# SAS_rev04.net
KiCad netlist of a schematic drawn in EAGLE
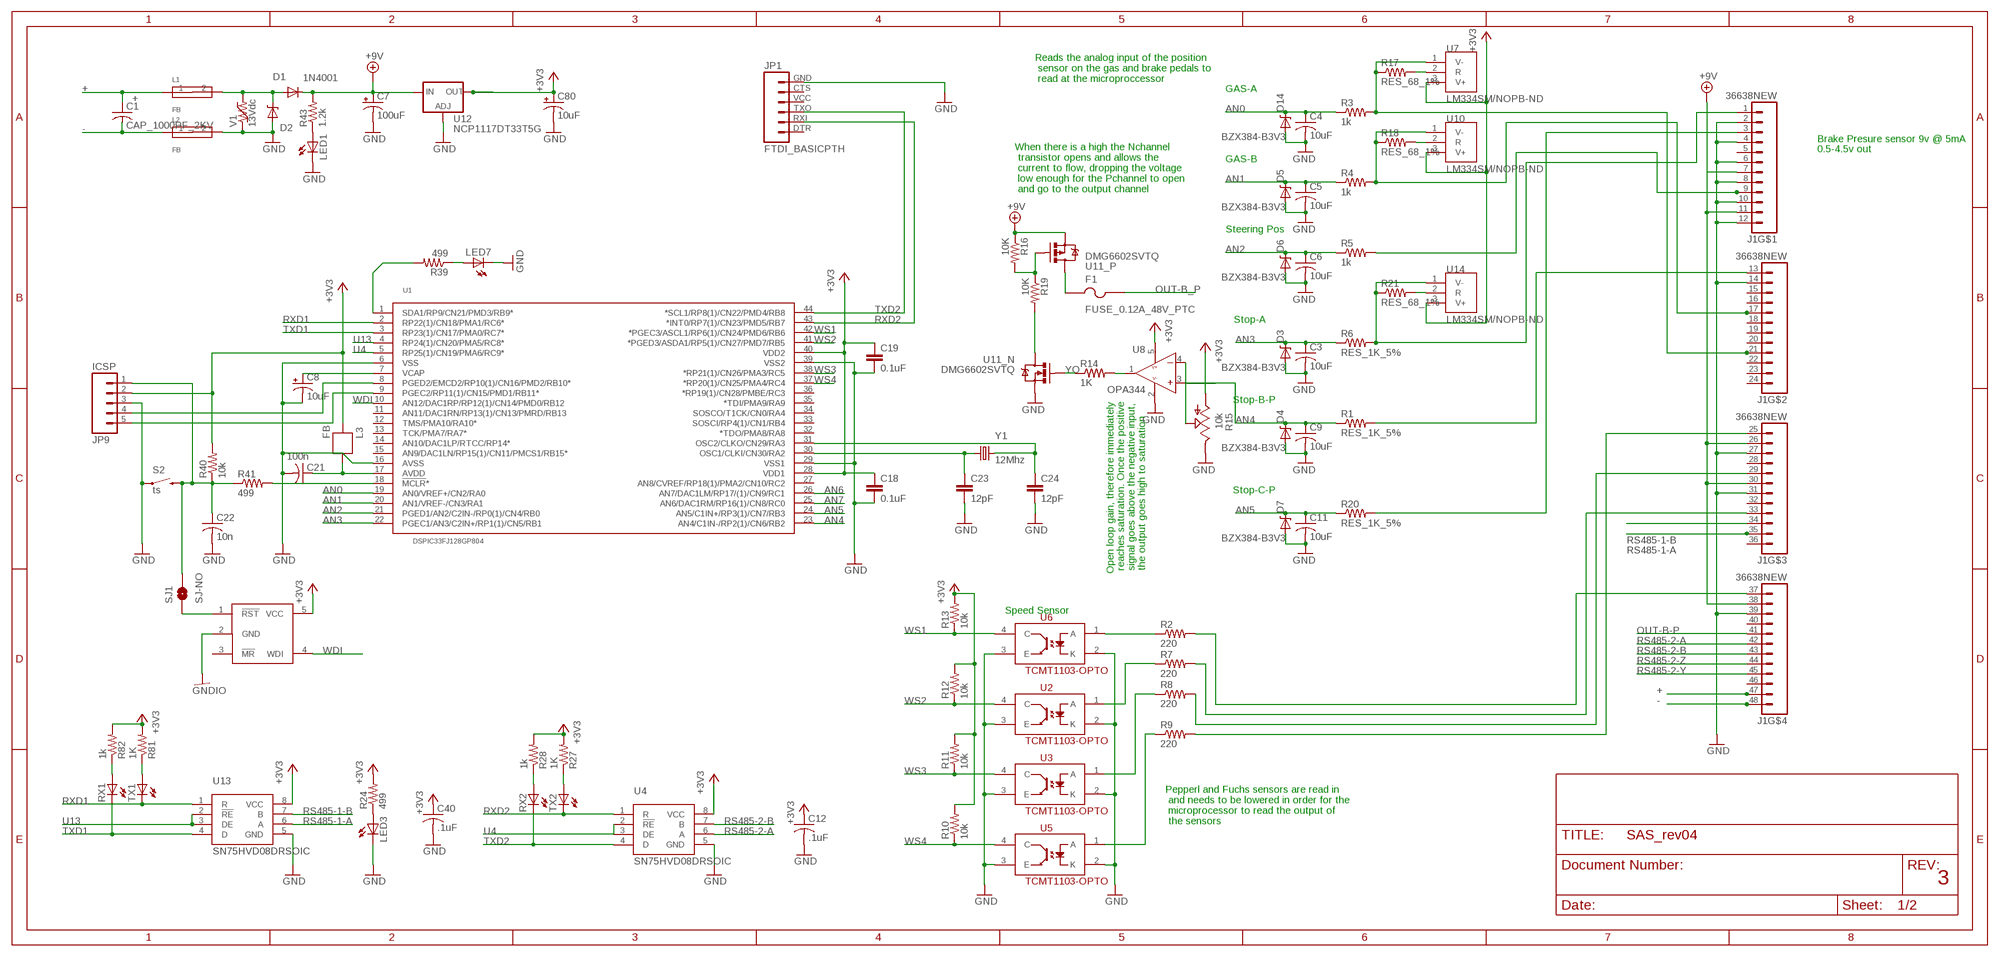
[diagram p0: schematic, sheet 1]

(export (version "E")
  (design (tool "Eeschema 10.0.6"))
  (components
    (comp (ref "C1")
      (value "CAP_1000PF_2KV")
      (footprint "eagle-import:C1825")
      (fields (field (name "PARTNO") "1825GC102KAT1A"))
      (libsource (lib "eagle-import") (part "CAP_1000PF_2KV"))
    )
    (comp (ref "C3")
      (value "10uF")
      (footprint "eagle-import:C0805")
      (libsource (lib "eagle-import") (part "C-USC0805"))
    )
    (comp (ref "C4")
      (value "10uF")
      (footprint "eagle-import:C0805")
      (libsource (lib "eagle-import") (part "C-USC0805"))
    )
    (comp (ref "C5")
      (value "10uF")
      (footprint "eagle-import:C0805")
      (libsource (lib "eagle-import") (part "C-USC0805"))
    )
    (comp (ref "C6")
      (value "10uF")
      (footprint "eagle-import:C0805")
      (libsource (lib "eagle-import") (part "C-USC0805"))
    )
    (comp (ref "C7")
      (value "100uF")
      (footprint "eagle-import:EIA7343")
      (libsource (lib "eagle-import") (part "CAP_POL7343"))
    )
    (comp (ref "C8")
      (value "10uF")
      (footprint "eagle-import:EIA3216-16V")
      (fields (field (name "PARTNO") "T491A106M016AT"))
      (libsource (lib "eagle-import") (part "CAP-POL_10UF_16V"))
    )
    (comp (ref "C9")
      (value "10uF")
      (footprint "eagle-import:C0805")
      (libsource (lib "eagle-import") (part "C-USC0805"))
    )
    (comp (ref "C11")
      (value "10uF")
      (footprint "eagle-import:C0805")
      (libsource (lib "eagle-import") (part "C-USC0805"))
    )
    (comp (ref "C12")
      (value ".1uF")
      (footprint "eagle-import:0603")
      (fields (field (name "PARTNO") "CC0603ZRY5V9BB104"))
      (libsource (lib "eagle-import") (part "CAP_0.1UF_50V"))
    )
    (comp (ref "C18")
      (value "0.1uF")
      (footprint "eagle-import:0805")
      (libsource (lib "eagle-import") (part "CAP0805"))
    )
    (comp (ref "C19")
      (value "0.1uF")
      (footprint "eagle-import:0805")
      (libsource (lib "eagle-import") (part "CAP0805"))
    )
    (comp (ref "C21")
      (value "100n")
      (footprint "eagle-import:C0805")
      (libsource (lib "eagle-import") (part "C-USC0805"))
    )
    (comp (ref "C22")
      (value "10n")
      (footprint "eagle-import:0603")
      (fields (field (name "PARTNO") "CL10F103ZB8NNNC"))
      (libsource (lib "eagle-import") (part "CAP_10NF_50V"))
    )
    (comp (ref "C23")
      (value "12pF")
      (footprint "eagle-import:0805")
      (libsource (lib "eagle-import") (part "CAP0805"))
    )
    (comp (ref "C24")
      (value "12pF")
      (footprint "eagle-import:0805")
      (libsource (lib "eagle-import") (part "CAP0805"))
    )
    (comp (ref "C40")
      (value ".1uF")
      (footprint "eagle-import:0603")
      (fields (field (name "PARTNO") "CC0603ZRY5V9BB104"))
      (libsource (lib "eagle-import") (part "CAP_0.1UF_50V"))
    )
    (comp (ref "C80")
      (value "10uF")
      (footprint "eagle-import:POLC1206")
      (libsource (lib "eagle-import") (part "POLCAP"))
    )
    (comp (ref "D1")
      (value "1N4001")
      (footprint "eagle-import:SOD123")
      (libsource (lib "eagle-import") (part "DIODE-SOD123"))
    )
    (comp (ref "D2")
      (value "MM5Z30")
      (footprint "eagle-import:SOD-523F")
      (libsource (lib "eagle-import") (part "MM5Z30"))
    )
    (comp (ref "D3")
      (value "BZX384-B3V3")
      (footprint "eagle-import:SOD-323")
      (libsource (lib "eagle-import") (part "DIODE-ZENER-BZT52"))
    )
    (comp (ref "D4")
      (value "BZX384-B3V3")
      (footprint "eagle-import:SOD-323")
      (libsource (lib "eagle-import") (part "DIODE-ZENER-BZT52"))
    )
    (comp (ref "D5")
      (value "BZX384-B3V3")
      (footprint "eagle-import:SOD-323")
      (libsource (lib "eagle-import") (part "DIODE-ZENER-BZT52"))
    )
    (comp (ref "D6")
      (value "BZX384-B3V3")
      (footprint "eagle-import:SOD-323")
      (libsource (lib "eagle-import") (part "DIODE-ZENER-BZT52"))
    )
    (comp (ref "D7")
      (value "BZX384-B3V3")
      (footprint "eagle-import:SOD-323")
      (libsource (lib "eagle-import") (part "DIODE-ZENER-BZT52"))
    )
    (comp (ref "D14")
      (value "BZX384-B3V3")
      (footprint "eagle-import:SOD-323")
      (libsource (lib "eagle-import") (part "DIODE-ZENER-BZT52"))
    )
    (comp (ref "F1")
      (value "FUSE_0.12A_48V_PTC")
      (footprint "eagle-import:1206")
      (fields (field (name "PARTNO") "0ZCJ0012FF2E"))
      (libsource (lib "eagle-import") (part "FUSE_0.12A_48V_PTC"))
    )
    (comp (ref "J1")
      (value "36638NEW")
      (footprint "eagle-import:36638-M")
      (libsource (lib "eagle-import") (part "36638NEW"))
    )
    (comp (ref "JP1")
      (value "FTDI_BASICPTH")
      (footprint "eagle-import:FTDI_BASIC")
      (libsource (lib "eagle-import") (part "FTDI_BASICPTH"))
    )
    (comp (ref "JP9")
      (value "ICSP")
      (footprint "eagle-import:1X05_LOCK_LONGPADS")
      (libsource (lib "eagle-import") (part "M05LOCK_LONGPADS"))
    )
    (comp (ref "L1")
      (value "FB")
      (footprint "eagle-import:0603")
      (libsource (lib "eagle-import") (part "FERITEBEAD"))
    )
    (comp (ref "L2")
      (value "FB")
      (footprint "eagle-import:0603")
      (libsource (lib "eagle-import") (part "FERITEBEAD"))
    )
    (comp (ref "L3")
      (value "FB")
      (footprint "eagle-import:0603")
      (libsource (lib "eagle-import") (part "FB"))
    )
    (comp (ref "LED1")
      (value "LEDCHIP-LED0805")
      (footprint "eagle-import:CHIP-LED0805")
      (libsource (lib "eagle-import") (part "LEDCHIP-LED0805"))
    )
    (comp (ref "LED3")
      (value "LEDCHIP-LED0805")
      (footprint "eagle-import:CHIP-LED0805")
      (libsource (lib "eagle-import") (part "LEDCHIP-LED0805"))
    )
    (comp (ref "LED7")
      (value "LEDCHIP-LED0805")
      (footprint "eagle-import:CHIP-LED0805")
      (libsource (lib "eagle-import") (part "LEDCHIP-LED0805"))
    )
    (comp (ref "R1")
      (value "RES_1K_5%")
      (footprint "eagle-import:0603")
      (fields (field (name "PARTNO") "RC0603JR-071KL"))
      (libsource (lib "eagle-import") (part "RES_1K_5%"))
    )
    (comp (ref "R2")
      (value "220")
      (footprint "eagle-import:0603")
      (fields (field (name "PARTNO") "RC0603FR-07220RL"))
      (libsource (lib "eagle-import") (part "RES_220_1%"))
    )
    (comp (ref "R3")
      (value "1k")
      (footprint "eagle-import:0603")
      (fields (field (name "PARTNO") "RC0603JR-071KL"))
      (libsource (lib "eagle-import") (part "RES_1K_5%"))
    )
    (comp (ref "R4")
      (value "1k")
      (footprint "eagle-import:0603")
      (fields (field (name "PARTNO") "RC0603JR-071KL"))
      (libsource (lib "eagle-import") (part "RES_1K_5%"))
    )
    (comp (ref "R5")
      (value "1k")
      (footprint "eagle-import:0603")
      (fields (field (name "PARTNO") "RC0603JR-071KL"))
      (libsource (lib "eagle-import") (part "RES_1K_5%"))
    )
    (comp (ref "R6")
      (value "RES_1K_5%")
      (footprint "eagle-import:0603")
      (fields (field (name "PARTNO") "RC0603JR-071KL"))
      (libsource (lib "eagle-import") (part "RES_1K_5%"))
    )
    (comp (ref "R7")
      (value "220")
      (footprint "eagle-import:0603")
      (fields (field (name "PARTNO") "RC0603FR-07220RL"))
      (libsource (lib "eagle-import") (part "RES_220_1%"))
    )
    (comp (ref "R8")
      (value "220")
      (footprint "eagle-import:0603")
      (fields (field (name "PARTNO") "RC0603FR-07220RL"))
      (libsource (lib "eagle-import") (part "RES_220_1%"))
    )
    (comp (ref "R9")
      (value "220")
      (footprint "eagle-import:0603")
      (fields (field (name "PARTNO") "RC0603FR-07220RL"))
      (libsource (lib "eagle-import") (part "RES_220_1%"))
    )
    (comp (ref "R10")
      (value "10k")
      (footprint "eagle-import:0603")
      (fields (field (name "PARTNO") "RC0603FR-0710KL"))
      (libsource (lib "eagle-import") (part "RES_10K_1%"))
    )
    (comp (ref "R11")
      (value "10k")
      (footprint "eagle-import:0603")
      (fields (field (name "PARTNO") "RC0603FR-0710KL"))
      (libsource (lib "eagle-import") (part "RES_10K_1%"))
    )
    (comp (ref "R12")
      (value "10k")
      (footprint "eagle-import:0603")
      (fields (field (name "PARTNO") "RC0603FR-0710KL"))
      (libsource (lib "eagle-import") (part "RES_10K_1%"))
    )
    (comp (ref "R13")
      (value "10k")
      (footprint "eagle-import:0603")
      (fields (field (name "PARTNO") "RC0603FR-0710KL"))
      (libsource (lib "eagle-import") (part "RES_10K_1%"))
    )
    (comp (ref "R14")
      (value "1K")
      (footprint "eagle-import:0805")
      (fields (field (name "PARTNO") "RC0805FR-071KL"))
      (libsource (lib "eagle-import") (part "RES_1K_1%_0805"))
    )
    (comp (ref "R15")
      (value "10k")
      (footprint "eagle-import:PVG3")
      (fields (field (name "PARTNO") "PVG3A103C01R00"))
      (libsource (lib "eagle-import") (part "POT_10K_POT"))
    )
    (comp (ref "R16")
      (value "10K")
      (footprint "eagle-import:0805")
      (fields (field (name "PARTNO") "RC0805FR-0710KL"))
      (libsource (lib "eagle-import") (part "RES_10K_1%_0805"))
    )
    (comp (ref "R17")
      (value "RES_68_1%")
      (footprint "eagle-import:0603")
      (fields (field (name "PARTNO") "CRCW060368R0FKEA"))
      (libsource (lib "eagle-import") (part "RES_68_1%"))
    )
    (comp (ref "R18")
      (value "RES_68_1%")
      (footprint "eagle-import:0603")
      (fields (field (name "PARTNO") "CRCW060368R0FKEA"))
      (libsource (lib "eagle-import") (part "RES_68_1%"))
    )
    (comp (ref "R19")
      (value "10K")
      (footprint "eagle-import:0805")
      (fields (field (name "PARTNO") "RC0805FR-0710KL"))
      (libsource (lib "eagle-import") (part "RES_10K_1%_0805"))
    )
    (comp (ref "R20")
      (value "RES_1K_5%")
      (footprint "eagle-import:0603")
      (fields (field (name "PARTNO") "RC0603JR-071KL"))
      (libsource (lib "eagle-import") (part "RES_1K_5%"))
    )
    (comp (ref "R21")
      (value "RES_68_1%")
      (footprint "eagle-import:0603")
      (fields (field (name "PARTNO") "CRCW060368R0FKEA"))
      (libsource (lib "eagle-import") (part "RES_68_1%"))
    )
    (comp (ref "R24")
      (value "499")
      (footprint "eagle-import:0603")
      (fields (field (name "PARTNO") "RC0603FR-07499RL"))
      (libsource (lib "eagle-import") (part "RES_499_1%"))
    )
    (comp (ref "R27")
      (value "1K")
      (footprint "eagle-import:0805")
      (fields (field (name "PARTNO") "RC0805FR-071KL"))
      (libsource (lib "eagle-import") (part "FSAE Eletric_RES_1K_1%_0805"))
    )
    (comp (ref "R28")
      (value "1k")
      (footprint "eagle-import:0805")
      (fields (field (name "PARTNO") "RC0805FR-071KL"))
      (libsource (lib "eagle-import") (part "FSAE Eletric_RES_1K_1%_0805"))
    )
    (comp (ref "R39")
      (value "499")
      (footprint "eagle-import:0603")
      (fields (field (name "PARTNO") "RC0603FR-07499RL"))
      (libsource (lib "eagle-import") (part "RES_499_1%"))
    )
    (comp (ref "R40")
      (value "10k")
      (footprint "eagle-import:0805")
      (fields (field (name "PARTNO") "RC0805FR-0710KL"))
      (libsource (lib "eagle-import") (part "FSAE Eletric_RES_10K_1%_0805"))
    )
    (comp (ref "R41")
      (value "499")
      (footprint "eagle-import:0805")
      (fields (field (name "PARTNO") "RC0805FR-07499RL"))
      (libsource (lib "eagle-import") (part "FSAE Eletric_RES_499_1%_0805"))
    )
    (comp (ref "R43")
      (value "1.2k")
      (footprint "eagle-import:0805")
      (fields (field (name "PARTNO") "RC0805FR-071K2L"))
      (libsource (lib "eagle-import") (part "RES_1.2K_1%_0805"))
    )
    (comp (ref "R81")
      (value "1K")
      (footprint "eagle-import:0603")
      (fields (field (name "PARTNO") "RC0603JR-071KL"))
      (libsource (lib "eagle-import") (part "RES_1K_5%"))
    )
    (comp (ref "R82")
      (value "1k")
      (footprint "eagle-import:0603")
      (fields (field (name "PARTNO") "RC0603JR-071KL"))
      (libsource (lib "eagle-import") (part "RES_1K_5%"))
    )
    (comp (ref "RX1")
      (value "LEDCHIPLED_0805")
      (footprint "eagle-import:CHIPLED_0805")
      (libsource (lib "eagle-import") (part "LEDCHIPLED_0805"))
    )
    (comp (ref "RX2")
      (value "LEDCHIPLED_0805")
      (footprint "eagle-import:CHIPLED_0805")
      (libsource (lib "eagle-import") (part "LEDCHIPLED_0805"))
    )
    (comp (ref "S2")
      (value "ts")
      (footprint "eagle-import:TACTILE-PTH")
      (libsource (lib "eagle-import") (part "SWITCH-MOMENTARY-2PTH"))
    )
    (comp (ref "SJ1")
      (value "SJ-NO")
      (footprint "eagle-import:SJ_2S-NO")
      (libsource (lib "eagle-import") (part "SOLDERJUMPERNO"))
    )
    (comp (ref "TX1")
      (value "LEDCHIPLED_0805")
      (footprint "eagle-import:CHIPLED_0805")
      (libsource (lib "eagle-import") (part "LEDCHIPLED_0805"))
    )
    (comp (ref "TX2")
      (value "LEDCHIPLED_0805")
      (footprint "eagle-import:CHIPLED_0805")
      (libsource (lib "eagle-import") (part "LEDCHIPLED_0805"))
    )
    (comp (ref "U1")
      (value "DSPIC33FJ128GP804")
      (footprint "eagle-import:TQFP-44")
      (fields (field (name "PARTNO") "DSPIC33FJ128GP804-I/PT"))
      (libsource (lib "eagle-import") (part "DSPIC33FJ128GP804"))
    )
    (comp (ref "U2")
      (value "TCMT1103-OPTO")
      (footprint "eagle-import:SSOP-4")
      (libsource (lib "eagle-import") (part "TCMT1103-OPTO"))
    )
    (comp (ref "U3")
      (value "TCMT1103-OPTO")
      (footprint "eagle-import:SSOP-4")
      (libsource (lib "eagle-import") (part "TCMT1103-OPTO"))
    )
    (comp (ref "U4")
      (value "SN75HVD08DRSOIC")
      (footprint "eagle-import:SO-8")
      (fields (field (name "PARTNO") "SN75176BDR"))
      (libsource (lib "eagle-import") (part "SN75HVD08DRSOIC"))
    )
    (comp (ref "U5")
      (value "TCMT1103-OPTO")
      (footprint "eagle-import:SSOP-4")
      (libsource (lib "eagle-import") (part "TCMT1103-OPTO"))
    )
    (comp (ref "U6")
      (value "TCMT1103-OPTO")
      (footprint "eagle-import:SSOP-4")
      (libsource (lib "eagle-import") (part "TCMT1103-OPTO"))
    )
    (comp (ref "U7")
      (value "LM334SM/NOPB-ND")
      (footprint "eagle-import:SO-8")
      (libsource (lib "eagle-import") (part "LM334SM/NOPB-ND"))
    )
    (comp (ref "U8")
      (value "OPA344")
      (footprint "eagle-import:SOT23-5")
      (fields (field (name "PARTNO") "OPA344NA/3K"))
      (libsource (lib "eagle-import") (part "OPA344"))
    )
    (comp (ref "U9")
      (value "MAX823")
      (footprint "eagle-import:SOT23-5L")
      (libsource (lib "eagle-import") (part "MAX823"))
    )
    (comp (ref "U10")
      (value "LM334SM/NOPB-ND")
      (footprint "eagle-import:SO-8")
      (libsource (lib "eagle-import") (part "LM334SM/NOPB-ND"))
    )
    (comp (ref "U11")
      (value "DMG6602SVTQ")
      (footprint "eagle-import:SOT23-6")
      (fields (field (name "PARTNO") "DMG6602SVTQ-7"))
      (libsource (lib "eagle-import") (part "DMG6602SVTQ"))
    )
    (comp (ref "U12")
      (value "NCP1117DT33T5G")
      (footprint "eagle-import:V-REG_DPACK")
      (libsource (lib "eagle-import") (part "V_REG_317DPACK"))
    )
    (comp (ref "U13")
      (value "SN75HVD08DRSOIC")
      (footprint "eagle-import:SO-8")
      (fields (field (name "PARTNO") "SN75176BDR"))
      (libsource (lib "eagle-import") (part "SN75HVD08DRSOIC"))
    )
    (comp (ref "U14")
      (value "LM334SM/NOPB-ND")
      (footprint "eagle-import:SO-8")
      (libsource (lib "eagle-import") (part "LM334SM/NOPB-ND"))
    )
    (comp (ref "V1")
      (value "13Vdc")
      (footprint "eagle-import:0603")
      (libsource (lib "eagle-import") (part "VAR-RES"))
    )
    (comp (ref "Y1")
      (value "12Mhz")
      (footprint "eagle-import:CRYSTAL-SMD-5X3")
      (libsource (lib "eagle-import") (part "CRYSTAL5X3"))
    )
  )
  (nets
    (net (code "1") (name "+") (class "Default")
      (node (ref "C1") (pin "1") (pinfunction "+_1") (pintype "passive"))
      (node (ref "J1") (pin "47") (pinfunction "11_47") (pintype "passive"))
      (node (ref "L1") (pin "1") (pinfunction "P$1_1") (pintype "bidirectional"))
    )
    (net (code "2") (name "+3V3") (class "Default")
      (node (ref "C12") (pin "1") (pinfunction "+_1") (pintype "passive"))
      (node (ref "C18") (pin "1") (pinfunction "1_1") (pintype "passive"))
      (node (ref "C19") (pin "1") (pinfunction "1_1") (pintype "passive"))
      (node (ref "C40") (pin "1") (pinfunction "+_1") (pintype "passive"))
      (node (ref "C80") (pin "1") (pinfunction "+_1") (pintype "passive"))
      (node (ref "JP9") (pin "2") (pinfunction "2_2") (pintype "passive"))
      (node (ref "L3") (pin "2") (pinfunction "P$2_2") (pintype "bidirectional"))
      (node (ref "R10") (pin "2") (pinfunction "2_2") (pintype "passive"))
      (node (ref "R11") (pin "2") (pinfunction "2_2") (pintype "passive"))
      (node (ref "R12") (pin "2") (pinfunction "2_2") (pintype "passive"))
      (node (ref "R13") (pin "2") (pinfunction "2_2") (pintype "passive"))
      (node (ref "R15") (pin "1") (pinfunction "CW_1") (pintype "passive"))
      (node (ref "R24") (pin "2") (pinfunction "2_2") (pintype "passive"))
      (node (ref "R27") (pin "2") (pinfunction "2_2") (pintype "passive"))
      (node (ref "R28") (pin "2") (pinfunction "2_2") (pintype "passive"))
      (node (ref "R40") (pin "2") (pinfunction "2_2") (pintype "passive"))
      (node (ref "R81") (pin "2") (pinfunction "2_2") (pintype "passive"))
      (node (ref "R82") (pin "2") (pinfunction "2_2") (pintype "passive"))
      (node (ref "U1") (pin "28") (pinfunction "VDD1_28") (pintype "bidirectional"))
      (node (ref "U1") (pin "40") (pinfunction "VDD2_40") (pintype "bidirectional"))
      (node (ref "U10") (pin "3") (pinfunction "V+_3") (pintype "bidirectional"))
      (node (ref "U12") (pin "4") (pinfunction "OUT_4") (pintype "output"))
      (node (ref "U13") (pin "8") (pinfunction "VCC_8") (pintype "bidirectional"))
      (node (ref "U14") (pin "3") (pinfunction "V+_3") (pintype "bidirectional"))
      (node (ref "U4") (pin "8") (pinfunction "VCC_8") (pintype "bidirectional"))
      (node (ref "U7") (pin "3") (pinfunction "V+_3") (pintype "bidirectional"))
      (node (ref "U8") (pin "5") (pinfunction "V+_5") (pintype "bidirectional"))
      (node (ref "U9") (pin "5") (pinfunction "VCC_5") (pintype "bidirectional"))
    )
    (net (code "3") (name "+9V") (class "Default")
      (node (ref "C7") (pin "A") (pinfunction "+_A") (pintype "passive"))
      (node (ref "D1") (pin "C") (pinfunction "C_C") (pintype "passive"))
      (node (ref "J1") (pin "11") (pinfunction "11_11") (pintype "passive"))
      (node (ref "J1") (pin "26") (pinfunction "2_26") (pintype "passive"))
      (node (ref "J1") (pin "30") (pinfunction "6_30") (pintype "passive"))
      (node (ref "J1") (pin "38") (pinfunction "2_38") (pintype "passive"))
      (node (ref "J1") (pin "7") (pinfunction "7_7") (pintype "passive"))
      (node (ref "R16") (pin "1") (pinfunction "1_1") (pintype "passive"))
      (node (ref "R43") (pin "2") (pinfunction "2_2") (pintype "passive"))
      (node (ref "U11") (pin "2") (pinfunction "S_2") (pintype "passive"))
      (node (ref "U12") (pin "3") (pinfunction "IN_3") (pintype "input"))
    )
    (net (code "4") (name "-") (class "Default")
      (node (ref "C1") (pin "2") (pinfunction "-_2") (pintype "passive"))
      (node (ref "J1") (pin "48") (pinfunction "12_48") (pintype "passive"))
      (node (ref "L2") (pin "1") (pinfunction "P$1_1") (pintype "bidirectional"))
    )
    (net (code "5") (name "AN0") (class "Default")
      (node (ref "C4") (pin "1") (pinfunction "1_1") (pintype "passive"))
      (node (ref "D14") (pin "1") (pinfunction "C_1") (pintype "passive"))
      (node (ref "R3") (pin "1") (pinfunction "1_1") (pintype "passive"))
      (node (ref "U1") (pin "19") (pinfunction "AN0/VREF+/CN2/RA0_19") (pintype "bidirectional"))
    )
    (net (code "6") (name "AN1") (class "Default")
      (node (ref "C5") (pin "1") (pinfunction "1_1") (pintype "passive"))
      (node (ref "D5") (pin "1") (pinfunction "C_1") (pintype "passive"))
      (node (ref "R4") (pin "1") (pinfunction "1_1") (pintype "passive"))
      (node (ref "U1") (pin "20") (pinfunction "AN1/VREF-/CN3/RA1_20") (pintype "bidirectional"))
    )
    (net (code "7") (name "AN2") (class "Default")
      (node (ref "C6") (pin "1") (pinfunction "1_1") (pintype "passive"))
      (node (ref "D6") (pin "1") (pinfunction "C_1") (pintype "passive"))
      (node (ref "R5") (pin "1") (pinfunction "1_1") (pintype "passive"))
      (node (ref "U1") (pin "21") (pinfunction "PGED1/AN2/C2IN-/RP0(1)/CN4/RB0_21") (pintype "bidirectional"))
    )
    (net (code "8") (name "AN3") (class "Default")
      (node (ref "C3") (pin "1") (pinfunction "1_1") (pintype "passive"))
      (node (ref "D3") (pin "1") (pinfunction "C_1") (pintype "passive"))
      (node (ref "R6") (pin "1") (pinfunction "1_1") (pintype "passive"))
      (node (ref "U1") (pin "22") (pinfunction "PGEC1/AN3/C2IN+/RP1(1)/CN5/RB1_22") (pintype "bidirectional"))
    )
    (net (code "9") (name "AN4") (class "Default")
      (node (ref "C9") (pin "1") (pinfunction "1_1") (pintype "passive"))
      (node (ref "D4") (pin "1") (pinfunction "C_1") (pintype "passive"))
      (node (ref "R1") (pin "1") (pinfunction "1_1") (pintype "passive"))
      (node (ref "U1") (pin "23") (pinfunction "AN4/C1IN-/RP2(1)/CN6/RB2_23") (pintype "bidirectional"))
      (node (ref "U8") (pin "3") (pinfunction "+_3") (pintype "bidirectional"))
    )
    (net (code "10") (name "AN5") (class "Default")
      (node (ref "C11") (pin "1") (pinfunction "1_1") (pintype "passive"))
      (node (ref "D7") (pin "1") (pinfunction "C_1") (pintype "passive"))
      (node (ref "R20") (pin "1") (pinfunction "1_1") (pintype "passive"))
      (node (ref "U1") (pin "24") (pinfunction "AN5/C1IN+/RP3(1)/CN7/RB3_24") (pintype "bidirectional"))
    )
    (net (code "11") (name "AN6") (class "Default")
      (node (ref "U1") (pin "26") (pinfunction "AN7/DAC1LM/RP17/(1)/CN9/RC1_26") (pintype "bidirectional"))
    )
    (net (code "12") (name "AN7") (class "Default")
      (node (ref "U1") (pin "25") (pinfunction "AN6/DAC1RM/RP16(1)/CN8/RC0_25") (pintype "bidirectional"))
    )
    (net (code "13") (name "GND") (class "Default")
      (node (ref "C11") (pin "2") (pinfunction "2_2") (pintype "passive"))
      (node (ref "C12") (pin "2") (pinfunction "-_2") (pintype "passive"))
      (node (ref "C18") (pin "2") (pinfunction "2_2") (pintype "passive"))
      (node (ref "C19") (pin "2") (pinfunction "2_2") (pintype "passive"))
      (node (ref "C21") (pin "2") (pinfunction "2_2") (pintype "passive"))
      (node (ref "C22") (pin "2") (pinfunction "-_2") (pintype "passive"))
      (node (ref "C23") (pin "2") (pinfunction "2_2") (pintype "passive"))
      (node (ref "C24") (pin "2") (pinfunction "2_2") (pintype "passive"))
      (node (ref "C3") (pin "2") (pinfunction "2_2") (pintype "passive"))
      (node (ref "C4") (pin "2") (pinfunction "2_2") (pintype "passive"))
      (node (ref "C40") (pin "2") (pinfunction "-_2") (pintype "passive"))
      (node (ref "C5") (pin "2") (pinfunction "2_2") (pintype "passive"))
      (node (ref "C6") (pin "2") (pinfunction "2_2") (pintype "passive"))
      (node (ref "C7") (pin "C") (pinfunction "-_C") (pintype "passive"))
      (node (ref "C8") (pin "C") (pinfunction "-_C") (pintype "passive"))
      (node (ref "C80") (pin "2") (pinfunction "-_2") (pintype "passive"))
      (node (ref "C9") (pin "2") (pinfunction "2_2") (pintype "passive"))
      (node (ref "D14") (pin "2") (pinfunction "A_2") (pintype "passive"))
      (node (ref "D2") (pin "A") (pinfunction "A_A") (pintype "passive"))
      (node (ref "D3") (pin "2") (pinfunction "A_2") (pintype "passive"))
      (node (ref "D4") (pin "2") (pinfunction "A_2") (pintype "passive"))
      (node (ref "D5") (pin "2") (pinfunction "A_2") (pintype "passive"))
      (node (ref "D6") (pin "2") (pinfunction "A_2") (pintype "passive"))
      (node (ref "D7") (pin "2") (pinfunction "A_2") (pintype "passive"))
      (node (ref "J1") (pin "10") (pinfunction "10_10") (pintype "passive"))
      (node (ref "J1") (pin "12") (pinfunction "12_12") (pintype "passive"))
      (node (ref "J1") (pin "14") (pinfunction "2_14") (pintype "passive"))
      (node (ref "J1") (pin "2") (pinfunction "2_2") (pintype "passive"))
      (node (ref "J1") (pin "27") (pinfunction "3_27") (pintype "passive"))
      (node (ref "J1") (pin "31") (pinfunction "7_31") (pintype "passive"))
      (node (ref "J1") (pin "39") (pinfunction "3_39") (pintype "passive"))
      (node (ref "J1") (pin "4") (pinfunction "4_4") (pintype "passive"))
      (node (ref "J1") (pin "6") (pinfunction "6_6") (pintype "passive"))
      (node (ref "J1") (pin "8") (pinfunction "8_8") (pintype "passive"))
      (node (ref "JP1") (pin "GND") (pinfunction "6_GND") (pintype "passive"))
      (node (ref "JP9") (pin "3") (pinfunction "3_3") (pintype "passive"))
      (node (ref "L2") (pin "2") (pinfunction "P$2_2") (pintype "bidirectional"))
      (node (ref "LED1") (pin "C") (pinfunction "C_C") (pintype "passive"))
      (node (ref "LED3") (pin "C") (pinfunction "C_C") (pintype "passive"))
      (node (ref "LED7") (pin "C") (pinfunction "C_C") (pintype "passive"))
      (node (ref "R15") (pin "3") (pinfunction "CCW_3") (pintype "passive"))
      (node (ref "S2") (pin "1") (pinfunction "1_1") (pintype "passive"))
      (node (ref "U1") (pin "16") (pinfunction "AVSS_16") (pintype "bidirectional"))
      (node (ref "U1") (pin "29") (pinfunction "VSS1_29") (pintype "bidirectional"))
      (node (ref "U1") (pin "39") (pinfunction "VSS2_39") (pintype "bidirectional"))
      (node (ref "U1") (pin "6") (pinfunction "VSS_6") (pintype "bidirectional"))
      (node (ref "U11") (pin "5") (pinfunction "S_5") (pintype "passive"))
      (node (ref "U12") (pin "1") (pinfunction "ADJ_1") (pintype "input"))
      (node (ref "U13") (pin "5") (pinfunction "GND_5") (pintype "bidirectional"))
      (node (ref "U2") (pin "2") (pinfunction "K_2") (pintype "bidirectional"))
      (node (ref "U2") (pin "3") (pinfunction "E_3") (pintype "bidirectional"))
      (node (ref "U3") (pin "2") (pinfunction "K_2") (pintype "bidirectional"))
      (node (ref "U3") (pin "3") (pinfunction "E_3") (pintype "bidirectional"))
      (node (ref "U4") (pin "5") (pinfunction "GND_5") (pintype "bidirectional"))
      (node (ref "U5") (pin "2") (pinfunction "K_2") (pintype "bidirectional"))
      (node (ref "U5") (pin "3") (pinfunction "E_3") (pintype "bidirectional"))
      (node (ref "U6") (pin "2") (pinfunction "K_2") (pintype "bidirectional"))
      (node (ref "U6") (pin "3") (pinfunction "E_3") (pintype "bidirectional"))
      (node (ref "U8") (pin "2") (pinfunction "V-_2") (pintype "bidirectional"))
      (node (ref "V1") (pin "1") (pinfunction "1_1") (pintype "passive"))
    )
    (net (code "14") (name "GNDIO") (class "Default")
      (node (ref "U9") (pin "2") (pinfunction "GND_2") (pintype "bidirectional"))
    )
    (net (code "15") (name "Net-(C8-+)") (class "Default")
      (node (ref "C8") (pin "A") (pinfunction "+_A") (pintype "passive"))
      (node (ref "U1") (pin "7") (pinfunction "VCAP_7") (pintype "bidirectional"))
    )
    (net (code "16") (name "Net-(C22-+)") (class "Default")
      (node (ref "C22") (pin "1") (pinfunction "+_1") (pintype "passive"))
      (node (ref "JP9") (pin "1") (pinfunction "1_1") (pintype "passive"))
      (node (ref "R40") (pin "1") (pinfunction "1_1") (pintype "passive"))
      (node (ref "R41") (pin "1") (pinfunction "1_1") (pintype "passive"))
      (node (ref "S2") (pin "3") (pinfunction "2_3") (pintype "passive"))
      (node (ref "SJ1") (pin "2") (pinfunction "2_2") (pintype "passive"))
    )
    (net (code "17") (name "Net-(F1-P$1)") (class "Default")
      (node (ref "F1") (pin "1") (pinfunction "P$1_1") (pintype "bidirectional"))
      (node (ref "U11") (pin "4") (pinfunction "D_4") (pintype "passive"))
    )
    (net (code "18") (name "Net-(J1-Pad3)") (class "Default")
      (node (ref "J1") (pin "3") (pinfunction "3_3") (pintype "passive"))
      (node (ref "R20") (pin "2") (pinfunction "2_2") (pintype "passive"))
    )
    (net (code "19") (name "Net-(J1-Pad9)") (class "Default")
      (node (ref "J1") (pin "9") (pinfunction "9_9") (pintype "passive"))
      (node (ref "R5") (pin "2") (pinfunction "2_2") (pintype "passive"))
    )
    (net (code "20") (name "Net-(J1B-1)") (class "Default")
      (node (ref "J1") (pin "13") (pinfunction "1_13") (pintype "passive"))
      (node (ref "R1") (pin "2") (pinfunction "2_2") (pintype "passive"))
    )
    (net (code "21") (name "Net-(J1B-5)") (class "Default")
      (node (ref "J1") (pin "17") (pinfunction "5_17") (pintype "passive"))
      (node (ref "R18") (pin "1") (pinfunction "1_1") (pintype "passive"))
      (node (ref "R4") (pin "2") (pinfunction "2_2") (pintype "passive"))
      (node (ref "U10") (pin "1") (pinfunction "V-_1") (pintype "bidirectional"))
    )
    (net (code "22") (name "Net-(J1B-9)") (class "Default")
      (node (ref "J1") (pin "21") (pinfunction "9_21") (pintype "passive"))
      (node (ref "R17") (pin "1") (pinfunction "1_1") (pintype "passive"))
      (node (ref "R3") (pin "2") (pinfunction "2_2") (pintype "passive"))
      (node (ref "U7") (pin "1") (pinfunction "V-_1") (pintype "bidirectional"))
    )
    (net (code "23") (name "Net-(J1C-1)") (class "Default")
      (node (ref "J1") (pin "25") (pinfunction "1_25") (pintype "passive"))
      (node (ref "R9") (pin "2") (pinfunction "2_2") (pintype "passive"))
    )
    (net (code "24") (name "Net-(J1C-5)") (class "Default")
      (node (ref "J1") (pin "29") (pinfunction "5_29") (pintype "passive"))
      (node (ref "R8") (pin "2") (pinfunction "2_2") (pintype "passive"))
    )
    (net (code "25") (name "Net-(J1C-9)") (class "Default")
      (node (ref "J1") (pin "33") (pinfunction "9_33") (pintype "passive"))
      (node (ref "R7") (pin "2") (pinfunction "2_2") (pintype "passive"))
    )
    (net (code "26") (name "Net-(J1D-1)") (class "Default")
      (node (ref "J1") (pin "37") (pinfunction "1_37") (pintype "passive"))
      (node (ref "R2") (pin "2") (pinfunction "2_2") (pintype "passive"))
    )
    (net (code "27") (name "Net-(L1-P$2)") (class "Default")
      (node (ref "D1") (pin "A") (pinfunction "A_A") (pintype "passive"))
      (node (ref "D2") (pin "C") (pinfunction "C_C") (pintype "passive"))
      (node (ref "L1") (pin "2") (pinfunction "P$2_2") (pintype "bidirectional"))
      (node (ref "V1") (pin "2") (pinfunction "2_2") (pintype "passive"))
    )
    (net (code "28") (name "Net-(L3-P$1)") (class "Default")
      (node (ref "C21") (pin "1") (pinfunction "1_1") (pintype "passive"))
      (node (ref "L3") (pin "1") (pinfunction "P$1_1") (pintype "bidirectional"))
      (node (ref "U1") (pin "17") (pinfunction "AVDD_17") (pintype "bidirectional"))
    )
    (net (code "29") (name "Net-(LED1-PadA)") (class "Default")
      (node (ref "LED1") (pin "A") (pinfunction "A_A") (pintype "passive"))
      (node (ref "R43") (pin "1") (pinfunction "1_1") (pintype "passive"))
    )
    (net (code "30") (name "Net-(LED3-PadA)") (class "Default")
      (node (ref "LED3") (pin "A") (pinfunction "A_A") (pintype "passive"))
      (node (ref "R24") (pin "1") (pinfunction "1_1") (pintype "passive"))
    )
    (net (code "31") (name "Net-(LED7-PadA)") (class "Default")
      (node (ref "LED7") (pin "A") (pinfunction "A_A") (pintype "passive"))
      (node (ref "R39") (pin "1") (pinfunction "1_1") (pintype "passive"))
    )
    (net (code "32") (name "Net-(R15-W)") (class "Default")
      (node (ref "R15") (pin "2") (pinfunction "W_2") (pintype "passive"))
      (node (ref "U8") (pin "4") (pinfunction "-_4") (pintype "bidirectional"))
    )
    (net (code "33") (name "Net-(R27-Pad1)") (class "Default")
      (node (ref "R27") (pin "1") (pinfunction "1_1") (pintype "passive"))
      (node (ref "TX2") (pin "A") (pinfunction "A_A") (pintype "passive"))
    )
    (net (code "34") (name "Net-(R28-Pad1)") (class "Default")
      (node (ref "R28") (pin "1") (pinfunction "1_1") (pintype "passive"))
      (node (ref "RX2") (pin "A") (pinfunction "A_A") (pintype "passive"))
    )
    (net (code "35") (name "Net-(R81-Pad1)") (class "Default")
      (node (ref "R81") (pin "1") (pinfunction "1_1") (pintype "passive"))
      (node (ref "TX1") (pin "A") (pinfunction "A_A") (pintype "passive"))
    )
    (net (code "36") (name "Net-(R82-Pad1)") (class "Default")
      (node (ref "R82") (pin "1") (pinfunction "1_1") (pintype "passive"))
      (node (ref "RX1") (pin "A") (pinfunction "A_A") (pintype "passive"))
    )
    (net (code "37") (name "Net-(U1-OSC1{slash}CLKI{slash}CN30{slash}RA2)") (class "Default")
      (node (ref "C23") (pin "1") (pinfunction "1_1") (pintype "passive"))
      (node (ref "U1") (pin "30") (pinfunction "OSC1/CLKI/CN30/RA2_30") (pintype "bidirectional"))
      (node (ref "Y1") (pin "1") (pinfunction "1_1") (pintype "passive"))
    )
    (net (code "38") (name "Net-(U1-OSC2{slash}CLKO{slash}CN29{slash}RA3)") (class "Default")
      (node (ref "C24") (pin "1") (pinfunction "1_1") (pintype "passive"))
      (node (ref "U1") (pin "31") (pinfunction "OSC2/CLKO/CN29/RA3_31") (pintype "bidirectional"))
      (node (ref "Y1") (pin "3") (pinfunction "2_3") (pintype "passive"))
    )
    (net (code "39") (name "Net-(U1-PGEC2{slash}RP11(1){slash}CN15{slash}PMD1{slash}RB11*)") (class "Default")
      (node (ref "JP9") (pin "5") (pinfunction "5_5") (pintype "passive"))
      (node (ref "U1") (pin "9") (pinfunction "PGEC2/RP11(1)/CN15/PMD1/RB11*_9") (pintype "bidirectional"))
    )
    (net (code "40") (name "Net-(U1-PGED2{slash}EMCD2{slash}RP10(1){slash}CN16{slash}PMD2{slash}RB10*)") (class "Default")
      (node (ref "JP9") (pin "4") (pinfunction "4_4") (pintype "passive"))
      (node (ref "U1") (pin "8") (pinfunction "PGED2/EMCD2/RP10(1)/CN16/PMD2/RB10*_8") (pintype "bidirectional"))
    )
    (net (code "41") (name "Net-(U1-SDA1{slash}RP9{slash}CN21{slash}PMD3{slash}RB9*)") (class "Default")
      (node (ref "R39") (pin "2") (pinfunction "2_2") (pintype "passive"))
      (node (ref "U1") (pin "1") (pinfunction "SDA1/RP9/CN21/PMD3/RB9*_1") (pintype "bidirectional"))
    )
    (net (code "42") (name "Net-(U1-~{MCLR}*)") (class "Default")
      (node (ref "R41") (pin "2") (pinfunction "2_2") (pintype "passive"))
      (node (ref "U1") (pin "18") (pinfunction "~{MCLR}*_18") (pintype "bidirectional"))
    )
    (net (code "43") (name "Net-(U2-A)") (class "Default")
      (node (ref "R7") (pin "1") (pinfunction "1_1") (pintype "passive"))
      (node (ref "U2") (pin "1") (pinfunction "A_1") (pintype "bidirectional"))
    )
    (net (code "44") (name "Net-(U3-A)") (class "Default")
      (node (ref "R8") (pin "1") (pinfunction "1_1") (pintype "passive"))
      (node (ref "U3") (pin "1") (pinfunction "A_1") (pintype "bidirectional"))
    )
    (net (code "45") (name "Net-(U5-A)") (class "Default")
      (node (ref "R9") (pin "1") (pinfunction "1_1") (pintype "passive"))
      (node (ref "U5") (pin "1") (pinfunction "A_1") (pintype "bidirectional"))
    )
    (net (code "46") (name "Net-(U6-A)") (class "Default")
      (node (ref "R2") (pin "1") (pinfunction "1_1") (pintype "passive"))
      (node (ref "U6") (pin "1") (pinfunction "A_1") (pintype "bidirectional"))
    )
    (net (code "47") (name "Net-(U7-R)") (class "Default")
      (node (ref "R17") (pin "2") (pinfunction "2_2") (pintype "passive"))
      (node (ref "U7") (pin "2") (pinfunction "R_2") (pintype "bidirectional"))
    )
    (net (code "48") (name "Net-(U8-O)") (class "Default")
      (node (ref "R14") (pin "2") (pinfunction "2_2") (pintype "passive"))
      (node (ref "U8") (pin "1") (pinfunction "O_1") (pintype "bidirectional"))
    )
    (net (code "49") (name "Net-(U9-~{RST})") (class "Default")
      (node (ref "SJ1") (pin "1") (pinfunction "1_1") (pintype "passive"))
      (node (ref "U9") (pin "1") (pinfunction "~{RST}_1") (pintype "bidirectional"))
    )
    (net (code "50") (name "Net-(U10-R)") (class "Default")
      (node (ref "R18") (pin "2") (pinfunction "2_2") (pintype "passive"))
      (node (ref "U10") (pin "2") (pinfunction "R_2") (pintype "bidirectional"))
    )
    (net (code "51") (name "Net-(U11A-D)") (class "Default")
      (node (ref "R19") (pin "2") (pinfunction "2_2") (pintype "passive"))
      (node (ref "U11") (pin "6") (pinfunction "D_6") (pintype "passive"))
    )
    (net (code "52") (name "Net-(U11B-G)") (class "Default")
      (node (ref "R16") (pin "2") (pinfunction "2_2") (pintype "passive"))
      (node (ref "R19") (pin "1") (pinfunction "1_1") (pintype "passive"))
      (node (ref "U11") (pin "3") (pinfunction "G_3") (pintype "passive"))
    )
    (net (code "53") (name "Net-(U14-R)") (class "Default")
      (node (ref "R21") (pin "2") (pinfunction "2_2") (pintype "passive"))
      (node (ref "U14") (pin "2") (pinfunction "R_2") (pintype "bidirectional"))
    )
    (net (code "54") (name "Net-(U14-V-)") (class "Default")
      (node (ref "J1") (pin "1") (pinfunction "1_1") (pintype "passive"))
      (node (ref "R21") (pin "1") (pinfunction "1_1") (pintype "passive"))
      (node (ref "R6") (pin "2") (pinfunction "2_2") (pintype "passive"))
      (node (ref "U14") (pin "1") (pinfunction "V-_1") (pintype "bidirectional"))
    )
    (net (code "55") (name "OUT-B-P") (class "Default")
      (node (ref "J1") (pin "41") (pinfunction "5_41") (pintype "passive"))
    )
    (net (code "56") (name "OUT-B_P") (class "Default")
      (node (ref "F1") (pin "2") (pinfunction "P$2_2") (pintype "bidirectional"))
    )
    (net (code "57") (name "RS485-1-A") (class "Default")
      (node (ref "J1") (pin "35") (pinfunction "11_35") (pintype "passive"))
      (node (ref "U13") (pin "6") (pinfunction "A_6") (pintype "bidirectional"))
    )
    (net (code "58") (name "RS485-1-B") (class "Default")
      (node (ref "J1") (pin "34") (pinfunction "10_34") (pintype "passive"))
      (node (ref "U13") (pin "7") (pinfunction "B_7") (pintype "bidirectional"))
    )
    (net (code "59") (name "RS485-2-A") (class "Default")
      (node (ref "J1") (pin "42") (pinfunction "6_42") (pintype "passive"))
      (node (ref "U4") (pin "6") (pinfunction "A_6") (pintype "bidirectional"))
    )
    (net (code "60") (name "RS485-2-B") (class "Default")
      (node (ref "J1") (pin "43") (pinfunction "7_43") (pintype "passive"))
      (node (ref "U4") (pin "7") (pinfunction "B_7") (pintype "bidirectional"))
    )
    (net (code "61") (name "RS485-2-Y") (class "Default")
      (node (ref "J1") (pin "45") (pinfunction "9_45") (pintype "passive"))
    )
    (net (code "62") (name "RS485-2-Z") (class "Default")
      (node (ref "J1") (pin "44") (pinfunction "8_44") (pintype "passive"))
    )
    (net (code "63") (name "RXD1") (class "Default")
      (node (ref "TX1") (pin "C") (pinfunction "C_C") (pintype "passive"))
      (node (ref "U1") (pin "2") (pinfunction "RP22(1)/CN18/PMA1/RC6*_2") (pintype "bidirectional"))
      (node (ref "U13") (pin "1") (pinfunction "R_1") (pintype "bidirectional"))
    )
    (net (code "64") (name "RXD2") (class "Default")
      (node (ref "JP1") (pin "RXI") (pinfunction "2_RXI") (pintype "passive"))
      (node (ref "TX2") (pin "C") (pinfunction "C_C") (pintype "passive"))
      (node (ref "U1") (pin "43") (pinfunction "*INT0/RP7(1)/CN23/PMD5/RB7_43") (pintype "bidirectional"))
      (node (ref "U4") (pin "1") (pinfunction "R_1") (pintype "bidirectional"))
    )
    (net (code "65") (name "TXD1") (class "Default")
      (node (ref "RX1") (pin "C") (pinfunction "C_C") (pintype "passive"))
      (node (ref "U1") (pin "3") (pinfunction "RP23(1)/CN17/PMA0/RC7*_3") (pintype "bidirectional"))
      (node (ref "U13") (pin "4") (pinfunction "D_4") (pintype "bidirectional"))
    )
    (net (code "66") (name "TXD2") (class "Default")
      (node (ref "JP1") (pin "TXO") (pinfunction "3_TXO") (pintype "passive"))
      (node (ref "RX2") (pin "C") (pinfunction "C_C") (pintype "passive"))
      (node (ref "U1") (pin "44") (pinfunction "*SCL1/RP8(1)/CN22/PMD4/RB8_44") (pintype "bidirectional"))
      (node (ref "U4") (pin "4") (pinfunction "D_4") (pintype "bidirectional"))
    )
    (net (code "67") (name "U4") (class "Default")
      (node (ref "U1") (pin "5") (pinfunction "RP25(1)/CN19/PMA6/RC9*_5") (pintype "bidirectional"))
      (node (ref "U4") (pin "2") (pinfunction "~{RE}_2") (pintype "bidirectional"))
      (node (ref "U4") (pin "3") (pinfunction "DE_3") (pintype "bidirectional"))
    )
    (net (code "68") (name "U13") (class "Default")
      (node (ref "U1") (pin "4") (pinfunction "RP24(1)/CN20/PMA5/RC8*_4") (pintype "bidirectional"))
      (node (ref "U13") (pin "2") (pinfunction "~{RE}_2") (pintype "bidirectional"))
      (node (ref "U13") (pin "3") (pinfunction "DE_3") (pintype "bidirectional"))
    )
    (net (code "69") (name "WDI") (class "Default")
      (node (ref "U1") (pin "10") (pinfunction "AN12/DAC1RP/RP12(1)/CN14/PMD0/RB12_10") (pintype "bidirectional"))
      (node (ref "U9") (pin "4") (pinfunction "WDI_4") (pintype "bidirectional"))
    )
    (net (code "70") (name "WS1") (class "Default")
      (node (ref "R13") (pin "1") (pinfunction "1_1") (pintype "passive"))
      (node (ref "U1") (pin "42") (pinfunction "*PGEC3/ASCL1/RP6(1)/CN24/PMD6/RB6_42") (pintype "bidirectional"))
      (node (ref "U6") (pin "4") (pinfunction "C_4") (pintype "bidirectional"))
    )
    (net (code "71") (name "WS2") (class "Default")
      (node (ref "R12") (pin "1") (pinfunction "1_1") (pintype "passive"))
      (node (ref "U1") (pin "41") (pinfunction "*PGED3/ASDA1/RP5(1)/CN27/PMD7/RB5_41") (pintype "bidirectional"))
      (node (ref "U2") (pin "4") (pinfunction "C_4") (pintype "bidirectional"))
    )
    (net (code "72") (name "WS3") (class "Default")
      (node (ref "R11") (pin "1") (pinfunction "1_1") (pintype "passive"))
      (node (ref "U1") (pin "38") (pinfunction "*RP21(1)/CN26/PMA3/RC5_38") (pintype "bidirectional"))
      (node (ref "U3") (pin "4") (pinfunction "C_4") (pintype "bidirectional"))
    )
    (net (code "73") (name "WS4") (class "Default")
      (node (ref "R10") (pin "1") (pinfunction "1_1") (pintype "passive"))
      (node (ref "U1") (pin "37") (pinfunction "*RP20(1)/CN25/PMA4/RC4_37") (pintype "bidirectional"))
      (node (ref "U5") (pin "4") (pinfunction "C_4") (pintype "bidirectional"))
    )
    (net (code "74") (name "YO") (class "Default")
      (node (ref "R14") (pin "1") (pinfunction "1_1") (pintype "passive"))
      (node (ref "U11") (pin "1") (pinfunction "G_1") (pintype "passive"))
    )
    (net (code "75") (name "unconnected-(J1-Pad5)") (class "Default")
      (node (ref "J1") (pin "5") (pinfunction "5_5") (pintype "passive"))
    )
    (net (code "76") (name "unconnected-(J1B-3-Pad15)") (class "Default")
      (node (ref "J1") (pin "15") (pinfunction "3_15") (pintype "passive"))
    )
    (net (code "77") (name "unconnected-(J1B-4-Pad16)") (class "Default")
      (node (ref "J1") (pin "16") (pinfunction "4_16") (pintype "passive"))
    )
    (net (code "78") (name "unconnected-(J1B-6-Pad18)") (class "Default")
      (node (ref "J1") (pin "18") (pinfunction "6_18") (pintype "passive"))
    )
    (net (code "79") (name "unconnected-(J1B-7-Pad19)") (class "Default")
      (node (ref "J1") (pin "19") (pinfunction "7_19") (pintype "passive"))
    )
    (net (code "80") (name "unconnected-(J1B-8-Pad20)") (class "Default")
      (node (ref "J1") (pin "20") (pinfunction "8_20") (pintype "passive"))
    )
    (net (code "81") (name "unconnected-(J1B-10-Pad22)") (class "Default")
      (node (ref "J1") (pin "22") (pinfunction "10_22") (pintype "passive"))
    )
    (net (code "82") (name "unconnected-(J1B-11-Pad23)") (class "Default")
      (node (ref "J1") (pin "23") (pinfunction "11_23") (pintype "passive"))
    )
    (net (code "83") (name "unconnected-(J1B-12-Pad24)") (class "Default")
      (node (ref "J1") (pin "24") (pinfunction "12_24") (pintype "passive"))
    )
    (net (code "84") (name "unconnected-(J1C-4-Pad28)") (class "Default")
      (node (ref "J1") (pin "28") (pinfunction "4_28") (pintype "passive"))
    )
    (net (code "85") (name "unconnected-(J1C-8-Pad32)") (class "Default")
      (node (ref "J1") (pin "32") (pinfunction "8_32") (pintype "passive"))
    )
    (net (code "86") (name "unconnected-(J1C-12-Pad36)") (class "Default")
      (node (ref "J1") (pin "36") (pinfunction "12_36") (pintype "passive"))
    )
    (net (code "87") (name "unconnected-(J1D-4-Pad40)") (class "Default")
      (node (ref "J1") (pin "40") (pinfunction "4_40") (pintype "passive"))
    )
    (net (code "88") (name "unconnected-(J1D-10-Pad46)") (class "Default")
      (node (ref "J1") (pin "46") (pinfunction "10_46") (pintype "passive"))
    )
    (net (code "89") (name "unconnected-(JP1-1-PadDTR)") (class "Default")
      (node (ref "JP1") (pin "DTR") (pinfunction "1_DTR") (pintype "passive"))
    )
    (net (code "90") (name "unconnected-(JP1-4-PadVCC)") (class "Default")
      (node (ref "JP1") (pin "VCC") (pinfunction "4_VCC") (pintype "passive"))
    )
    (net (code "91") (name "unconnected-(JP1-5-PadCTS)") (class "Default")
      (node (ref "JP1") (pin "CTS") (pinfunction "5_CTS") (pintype "passive"))
    )
    (net (code "92") (name "unconnected-(U1-*RP19(1){slash}CN28{slash}PMBE{slash}RC3-Pad36)") (class "Default")
      (node (ref "U1") (pin "36") (pinfunction "*RP19(1)/CN28/PMBE/RC3_36") (pintype "bidirectional"))
    )
    (net (code "93") (name "unconnected-(U1-*TDI{slash}PMA9{slash}RA9-Pad35)") (class "Default")
      (node (ref "U1") (pin "35") (pinfunction "*TDI/PMA9/RA9_35") (pintype "bidirectional"))
    )
    (net (code "94") (name "unconnected-(U1-*TDO{slash}PMA8{slash}RA8-Pad32)") (class "Default")
      (node (ref "U1") (pin "32") (pinfunction "*TDO/PMA8/RA8_32") (pintype "bidirectional"))
    )
    (net (code "95") (name "unconnected-(U1-AN8{slash}CVREF{slash}RP18(1){slash}PMA2{slash}CN10{slash}RC2-Pad27)") (class "Default")
      (node (ref "U1") (pin "27") (pinfunction "AN8/CVREF/RP18(1)/PMA2/CN10/RC2_27") (pintype "bidirectional"))
    )
    (net (code "96") (name "unconnected-(U1-AN9{slash}DAC1LN{slash}RP15(1){slash}CN11{slash}PMCS1{slash}RB15*-Pad15)") (class "Default")
      (node (ref "U1") (pin "15") (pinfunction "AN9/DAC1LN/RP15(1)/CN11/PMCS1/RB15*_15") (pintype "bidirectional"))
    )
    (net (code "97") (name "unconnected-(U1-AN10{slash}DAC1LP{slash}RTCC{slash}RP14*-Pad14)") (class "Default")
      (node (ref "U1") (pin "14") (pinfunction "AN10/DAC1LP/RTCC/RP14*_14") (pintype "bidirectional"))
    )
    (net (code "98") (name "unconnected-(U1-AN11{slash}DAC1RN{slash}RP13(1){slash}CN13{slash}PMRD{slash}RB13-Pad11)") (class "Default")
      (node (ref "U1") (pin "11") (pinfunction "AN11/DAC1RN/RP13(1)/CN13/PMRD/RB13_11") (pintype "bidirectional"))
    )
    (net (code "99") (name "unconnected-(U1-SOSCI{slash}RP4(1){slash}CN1{slash}RB4-Pad33)") (class "Default")
      (node (ref "U1") (pin "33") (pinfunction "SOSCI/RP4(1)/CN1/RB4_33") (pintype "bidirectional"))
    )
    (net (code "100") (name "unconnected-(U1-SOSCO{slash}T1CK{slash}CN0{slash}RA4-Pad34)") (class "Default")
      (node (ref "U1") (pin "34") (pinfunction "SOSCO/T1CK/CN0/RA4_34") (pintype "bidirectional"))
    )
    (net (code "101") (name "unconnected-(U1-TCK{slash}PMA7{slash}RA7*-Pad13)") (class "Default")
      (node (ref "U1") (pin "13") (pinfunction "TCK/PMA7/RA7*_13") (pintype "bidirectional"))
    )
    (net (code "102") (name "unconnected-(U1-TMS{slash}PMA10{slash}RA10*-Pad12)") (class "Default")
      (node (ref "U1") (pin "12") (pinfunction "TMS/PMA10/RA10*_12") (pintype "bidirectional"))
    )
    (net (code "103") (name "unconnected-(U9-~{MR}-Pad3)") (class "Default")
      (node (ref "U9") (pin "3") (pinfunction "~{MR}_3") (pintype "bidirectional"))
    )
  )
)
